# Ex_FTDI_Cable.net
KiCad netlist of a schematic drawn in EAGLE
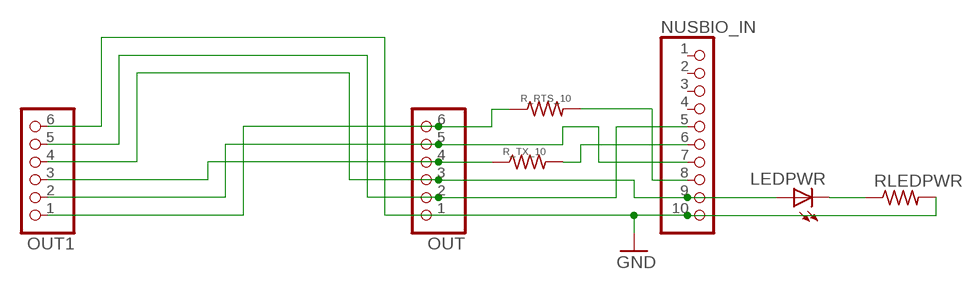
[diagram p0: schematic, sheet 1]

(export (version "E")
  (design (tool "Eeschema 10.0.6"))
  (components
    (comp (ref "LEDPWR")
      (value "LEDCHIPLED_0805")
      (footprint "eagle-import:CHIPLED_0805")
      (libsource (lib "eagle-import") (part "LEDCHIPLED_0805"))
    )
    (comp (ref "NUSBIO_IN")
      (value "PINHD-1X10")
      (footprint "eagle-import:1X10-BIG")
      (libsource (lib "eagle-import") (part "PINHD-1X10"))
    )
    (comp (ref "OUT")
      (value "PINHD-1X6")
      (footprint "eagle-import:1X06")
      (libsource (lib "eagle-import") (part "PINHD-1X6"))
    )
    (comp (ref "OUT1")
      (value "PINHD-1X6")
      (footprint "eagle-import:1X06")
      (libsource (lib "eagle-import") (part "PINHD-1X6"))
    )
    (comp (ref "RLEDPWR")
      (value "R-US_R0805")
      (footprint "eagle-import:R0805")
      (libsource (lib "eagle-import") (part "R-US_R0805"))
    )
    (comp (ref "R_RTS_10")
      (value "R-US_R0805")
      (footprint "eagle-import:R0805")
      (libsource (lib "eagle-import") (part "R-US_R0805"))
    )
    (comp (ref "R_TX_10")
      (value "R-US_R0805")
      (footprint "eagle-import:R0805")
      (libsource (lib "eagle-import") (part "R-US_R0805"))
    )
  )
  (nets
    (net (code "1") (name "GND") (class "Default")
      (node (ref "NUSBIO_IN") (pin "10") (pinfunction "10_10") (pintype "passive"))
      (node (ref "OUT") (pin "1") (pinfunction "1_1") (pintype "passive"))
      (node (ref "OUT1") (pin "6") (pinfunction "6_6") (pintype "passive"))
      (node (ref "RLEDPWR") (pin "2") (pinfunction "2_2") (pintype "passive"))
    )
    (net (code "2") (name "Net-(LEDPWR-PadA)") (class "Default")
      (node (ref "LEDPWR") (pin "A") (pinfunction "A_A") (pintype "passive"))
      (node (ref "NUSBIO_IN") (pin "9") (pinfunction "9_9") (pintype "passive"))
      (node (ref "OUT") (pin "3") (pinfunction "3_3") (pintype "passive"))
      (node (ref "OUT1") (pin "4") (pinfunction "4_4") (pintype "passive"))
    )
    (net (code "3") (name "Net-(LEDPWR-PadC)") (class "Default")
      (node (ref "LEDPWR") (pin "C") (pinfunction "C_C") (pintype "passive"))
      (node (ref "RLEDPWR") (pin "1") (pinfunction "1_1") (pintype "passive"))
    )
    (net (code "4") (name "Net-(NUSBIO_IN-Pad5)") (class "Default")
      (node (ref "NUSBIO_IN") (pin "5") (pinfunction "5_5") (pintype "passive"))
      (node (ref "OUT") (pin "2") (pinfunction "2_2") (pintype "passive"))
      (node (ref "OUT1") (pin "5") (pinfunction "5_5") (pintype "passive"))
    )
    (net (code "5") (name "Net-(NUSBIO_IN-Pad6)") (class "Default")
      (node (ref "NUSBIO_IN") (pin "6") (pinfunction "6_6") (pintype "passive"))
      (node (ref "R_TX_10") (pin "2") (pinfunction "2_2") (pintype "passive"))
    )
    (net (code "6") (name "Net-(NUSBIO_IN-Pad7)") (class "Default")
      (node (ref "NUSBIO_IN") (pin "7") (pinfunction "7_7") (pintype "passive"))
      (node (ref "OUT") (pin "5") (pinfunction "5_5") (pintype "passive"))
      (node (ref "OUT1") (pin "2") (pinfunction "2_2") (pintype "passive"))
    )
    (net (code "7") (name "Net-(NUSBIO_IN-Pad8)") (class "Default")
      (node (ref "NUSBIO_IN") (pin "8") (pinfunction "8_8") (pintype "passive"))
      (node (ref "R_RTS_10") (pin "2") (pinfunction "2_2") (pintype "passive"))
    )
    (net (code "8") (name "Net-(OUT-Pad4)") (class "Default")
      (node (ref "OUT") (pin "4") (pinfunction "4_4") (pintype "passive"))
      (node (ref "OUT1") (pin "3") (pinfunction "3_3") (pintype "passive"))
      (node (ref "R_TX_10") (pin "1") (pinfunction "1_1") (pintype "passive"))
    )
    (net (code "9") (name "Net-(OUT-Pad6)") (class "Default")
      (node (ref "OUT") (pin "6") (pinfunction "6_6") (pintype "passive"))
      (node (ref "OUT1") (pin "1") (pinfunction "1_1") (pintype "passive"))
      (node (ref "R_RTS_10") (pin "1") (pinfunction "1_1") (pintype "passive"))
    )
    (net (code "10") (name "unconnected-(NUSBIO_IN-Pad1)") (class "Default")
      (node (ref "NUSBIO_IN") (pin "1") (pinfunction "1_1") (pintype "passive"))
    )
    (net (code "11") (name "unconnected-(NUSBIO_IN-Pad2)") (class "Default")
      (node (ref "NUSBIO_IN") (pin "2") (pinfunction "2_2") (pintype "passive"))
    )
    (net (code "12") (name "unconnected-(NUSBIO_IN-Pad3)") (class "Default")
      (node (ref "NUSBIO_IN") (pin "3") (pinfunction "3_3") (pintype "passive"))
    )
    (net (code "13") (name "unconnected-(NUSBIO_IN-Pad4)") (class "Default")
      (node (ref "NUSBIO_IN") (pin "4") (pinfunction "4_4") (pintype "passive"))
    )
  )
)
